# aq_mx_v1-4-0b.net
KiCad netlist of a schematic drawn in EAGLE
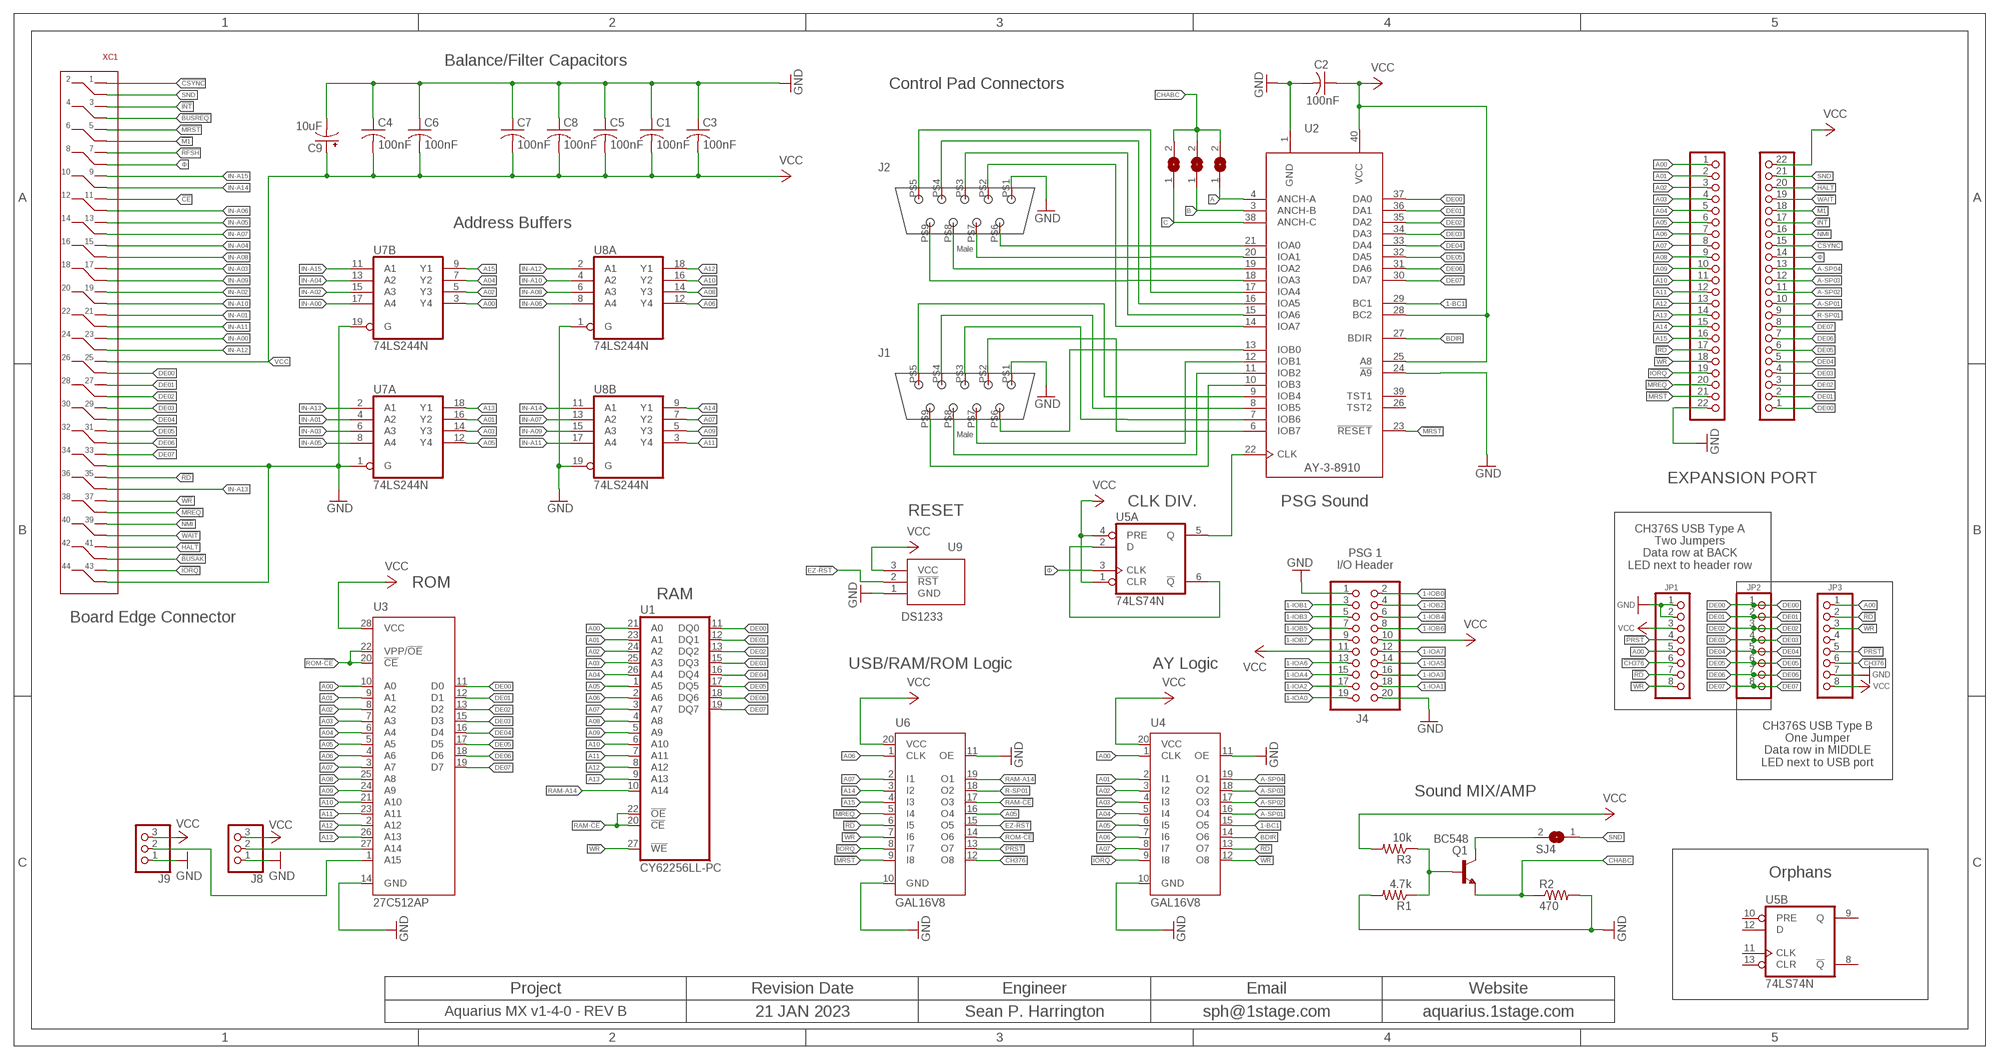
[diagram p0: schematic, sheet 1]

(export (version "E")
  (design (tool "Eeschema 10.0.6"))
  (components
    (comp (ref "C1")
      (value "100nF")
      (footprint "eagle-import:C050-025X075")
      (libsource (lib "eagle-import") (part "C-US050-025X075"))
    )
    (comp (ref "C2")
      (value "100nF")
      (footprint "eagle-import:C050-025X075")
      (libsource (lib "eagle-import") (part "C-US050-025X075"))
    )
    (comp (ref "C3")
      (value "100nF")
      (footprint "eagle-import:C050-025X075")
      (libsource (lib "eagle-import") (part "C-US050-025X075"))
    )
    (comp (ref "C4")
      (value "100nF")
      (footprint "eagle-import:C050-025X075")
      (libsource (lib "eagle-import") (part "C-US050-025X075"))
    )
    (comp (ref "C5")
      (value "100nF")
      (footprint "eagle-import:C050-025X075")
      (libsource (lib "eagle-import") (part "C-US050-025X075"))
    )
    (comp (ref "C6")
      (value "100nF")
      (footprint "eagle-import:C050-025X075")
      (libsource (lib "eagle-import") (part "C-US050-025X075"))
    )
    (comp (ref "C7")
      (value "100nF")
      (footprint "eagle-import:C050-025X075")
      (libsource (lib "eagle-import") (part "C-US050-025X075"))
    )
    (comp (ref "C8")
      (value "100nF")
      (footprint "eagle-import:C050-025X075")
      (libsource (lib "eagle-import") (part "C-US050-025X075"))
    )
    (comp (ref "C9")
      (value "10uF")
      (footprint "eagle-import:E22-6")
      (libsource (lib "eagle-import") (part "CPOL-USE22-6AXIAL"))
    )
    (comp (ref "J1")
      (value "DB9-MALE-RA")
      (footprint "eagle-import:DB9-MALE-RA")
      (libsource (lib "eagle-import") (part "DB9-MALE-RA"))
    )
    (comp (ref "J2")
      (value "DB9-MALE-RA")
      (footprint "eagle-import:DB9-MALE-RA")
      (libsource (lib "eagle-import") (part "DB9-MALE-RA"))
    )
    (comp (ref "J4")
      (value "PINHD-2X10")
      (footprint "eagle-import:2X10")
      (libsource (lib "eagle-import") (part "PINHD-2X10"))
    )
    (comp (ref "J6")
      (value "PINHD-1X22")
      (footprint "eagle-import:1X22")
      (libsource (lib "eagle-import") (part "PINHD-1X22"))
    )
    (comp (ref "J7")
      (value "PINHD-1X22")
      (footprint "eagle-import:1X22")
      (libsource (lib "eagle-import") (part "PINHD-1X22"))
    )
    (comp (ref "J8")
      (value "PINHD-1X3")
      (footprint "eagle-import:1X03")
      (libsource (lib "eagle-import") (part "PINHD-1X3"))
    )
    (comp (ref "J9")
      (value "PINHD-1X3")
      (footprint "eagle-import:1X03")
      (libsource (lib "eagle-import") (part "PINHD-1X3"))
    )
    (comp (ref "JP1")
      (value "PINHD-1X8")
      (footprint "eagle-import:1X08")
      (libsource (lib "eagle-import") (part "PINHD-1X8"))
    )
    (comp (ref "JP2")
      (value "PINHD-1X8")
      (footprint "eagle-import:1X08")
      (libsource (lib "eagle-import") (part "PINHD-1X8"))
    )
    (comp (ref "JP3")
      (value "PINHD-1X8")
      (footprint "eagle-import:1X08")
      (libsource (lib "eagle-import") (part "PINHD-1X8"))
    )
    (comp (ref "Q1")
      (value "BC548")
      (footprint "eagle-import:TO92-CBE")
      (libsource (lib "eagle-import") (part "-NPN-TO92-CBEBC548"))
    )
    (comp (ref "R1")
      (value "4.7k")
      (footprint "eagle-import:0204_7")
      (libsource (lib "eagle-import") (part "R-US_0204/7"))
    )
    (comp (ref "R2")
      (value "470")
      (footprint "eagle-import:0204_7")
      (libsource (lib "eagle-import") (part "R-US_0204/7"))
    )
    (comp (ref "R3")
      (value "10k")
      (footprint "eagle-import:0204_7")
      (libsource (lib "eagle-import") (part "R-US_0204/7"))
    )
    (comp (ref "SJ1") (value "SJ") (footprint "eagle-import:SJ") (libsource (lib "eagle-import") (part "SJ")))
    (comp (ref "SJ2") (value "SJ") (footprint "eagle-import:SJ") (libsource (lib "eagle-import") (part "SJ")))
    (comp (ref "SJ3") (value "SJ") (footprint "eagle-import:SJ") (libsource (lib "eagle-import") (part "SJ")))
    (comp (ref "SJ4") (value "SJ") (footprint "eagle-import:SJ") (libsource (lib "eagle-import") (part "SJ")))
    (comp (ref "U1")
      (value "CY62256LL-PC")
      (footprint "eagle-import:DIL28-6")
      (libsource (lib "eagle-import") (part "CY62256LL-?PC"))
    )
    (comp (ref "U2")
      (value "AY-3-8910")
      (footprint "eagle-import:RAD38910-DIL40-6")
      (libsource (lib "eagle-import") (part "RAD38910DIL40-6"))
    )
    (comp (ref "U3")
      (value "27C512AP")
      (footprint "eagle-import:DIL28-6")
      (fields (field (name "MPN") "M27C512-90B6"))
      (libsource (lib "eagle-import") (part "27512APC"))
    )
    (comp (ref "U4")
      (value "GAL16V8")
      (footprint "eagle-import:DIL20")
      (fields (field (name "MPN") "ATF16V8CZ-15PU"))
      (libsource (lib "eagle-import") (part "ATF16V8BP3"))
    )
    (comp (ref "U5")
      (value "74LS74N")
      (footprint "eagle-import:DIL14")
      (libsource (lib "eagle-import") (part "7474NLS"))
    )
    (comp (ref "U6")
      (value "GAL16V8")
      (footprint "eagle-import:DIL20")
      (fields (field (name "MPN") "ATF16V8CZ-15PU"))
      (libsource (lib "eagle-import") (part "ATF16V8BP3"))
    )
    (comp (ref "U7")
      (value "74LS244N")
      (footprint "eagle-import:DIL20")
      (libsource (lib "eagle-import") (part "74244NLS"))
    )
    (comp (ref "U8")
      (value "74LS244N")
      (footprint "eagle-import:DIL20")
      (libsource (lib "eagle-import") (part "74244NLS"))
    )
    (comp (ref "U9")
      (value "DS1233")
      (footprint "eagle-import:TO-92")
      (fields
        (field (name "ARROW_PART_NUMBER") "DS1233-10+")
        (field (name "MOUSER_PART_NUMBER") "700-DS1233-10")
      )
      (libsource (lib "eagle-import") (part "DS1233-10+"))
    )
    (comp (ref "XC1")
      (value "AQ-CART-EDGE")
      (footprint "eagle-import:AQ-CART-EDGE")
      (libsource (lib "eagle-import") (part "AQ-CART-EDGE"))
    )
  )
  (nets
    (net (code "1") (name "/EZ-~{RST}") (class "Default")
      (node (ref "U6") (pin "15") (pinfunction "O5_15") (pintype "output"))
      (node (ref "U9") (pin "2") (pinfunction "~{RST}_2") (pintype "input"))
    )
    (net (code "2") (name "/RAM-~{CE}") (class "Default")
      (node (ref "U1") (pin "20") (pinfunction "~{CE}_20") (pintype "input"))
      (node (ref "U1") (pin "22") (pinfunction "~{OE}_22") (pintype "input"))
      (node (ref "U6") (pin "17") (pinfunction "O3_17") (pintype "output"))
    )
    (net (code "3") (name "/ROM-~{CE}") (class "Default")
      (node (ref "U3") (pin "20") (pinfunction "~{CE}_20") (pintype "input"))
      (node (ref "U3") (pin "22") (pinfunction "VPP/~{OE}_22") (pintype "input"))
      (node (ref "U6") (pin "14") (pinfunction "O6_14") (pintype "output"))
    )
    (net (code "4") (name "/~{BUSAK}") (class "Default")
      (node (ref "XC1") (pin "P$42") (pinfunction "X42_P$42") (pintype "bidirectional"))
    )
    (net (code "5") (name "/~{BUSREQ}") (class "Default")
      (node (ref "XC1") (pin "P$4") (pinfunction "X4_P$4") (pintype "bidirectional"))
    )
    (net (code "6") (name "/~{CE}") (class "Default")
      (node (ref "XC1") (pin "P$11") (pinfunction "X11_P$11") (pintype "bidirectional"))
    )
    (net (code "7") (name "/~{CH376}") (class "Default")
      (node (ref "JP1") (pin "6") (pinfunction "6_6") (pintype "passive"))
      (node (ref "JP3") (pin "6") (pinfunction "6_6") (pintype "passive"))
      (node (ref "U6") (pin "12") (pinfunction "O8_12") (pintype "output"))
    )
    (net (code "8") (name "/~{CSYNC}") (class "Default")
      (node (ref "J6") (pin "15") (pinfunction "15_15") (pintype "passive"))
      (node (ref "XC1") (pin "P$1") (pinfunction "X1_P$1") (pintype "bidirectional"))
    )
    (net (code "9") (name "/~{HALT}") (class "Default")
      (node (ref "J6") (pin "20") (pinfunction "20_20") (pintype "passive"))
      (node (ref "XC1") (pin "P$41") (pinfunction "X41_P$41") (pintype "bidirectional"))
    )
    (net (code "10") (name "/~{INT}") (class "Default")
      (node (ref "J6") (pin "17") (pinfunction "17_17") (pintype "passive"))
      (node (ref "XC1") (pin "P$3") (pinfunction "X3_P$3") (pintype "bidirectional"))
    )
    (net (code "11") (name "/~{IORQ}") (class "Default")
      (node (ref "J7") (pin "19") (pinfunction "19_19") (pintype "passive"))
      (node (ref "U4") (pin "9") (pinfunction "I8_9") (pintype "input"))
      (node (ref "U6") (pin "8") (pinfunction "I7_8") (pintype "input"))
      (node (ref "XC1") (pin "P$43") (pinfunction "X43_P$43") (pintype "bidirectional"))
    )
    (net (code "12") (name "/~{M1}") (class "Default")
      (node (ref "J6") (pin "18") (pinfunction "18_18") (pintype "passive"))
      (node (ref "XC1") (pin "P$6") (pinfunction "X6_P$6") (pintype "bidirectional"))
    )
    (net (code "13") (name "/~{MREQ}") (class "Default")
      (node (ref "J7") (pin "20") (pinfunction "20_20") (pintype "passive"))
      (node (ref "U6") (pin "5") (pinfunction "I4_5") (pintype "input"))
      (node (ref "XC1") (pin "P$38") (pinfunction "X38_P$38") (pintype "bidirectional"))
    )
    (net (code "14") (name "/~{MRST}") (class "Default")
      (node (ref "J7") (pin "21") (pinfunction "21_21") (pintype "passive"))
      (node (ref "U2") (pin "23") (pinfunction "~{RESET}_23") (pintype "bidirectional"))
      (node (ref "U6") (pin "9") (pinfunction "I8_9") (pintype "input"))
      (node (ref "XC1") (pin "P$5") (pinfunction "X5_P$5") (pintype "bidirectional"))
    )
    (net (code "15") (name "/~{NMI}") (class "Default")
      (node (ref "J6") (pin "16") (pinfunction "16_16") (pintype "passive"))
      (node (ref "XC1") (pin "P$39") (pinfunction "X39_P$39") (pintype "bidirectional"))
    )
    (net (code "16") (name "/~{PRST}") (class "Default")
      (node (ref "JP1") (pin "4") (pinfunction "4_4") (pintype "passive"))
      (node (ref "JP3") (pin "5") (pinfunction "5_5") (pintype "passive"))
      (node (ref "U6") (pin "13") (pinfunction "O7_13") (pintype "output"))
    )
    (net (code "17") (name "/~{RD}") (class "Default")
      (node (ref "J7") (pin "17") (pinfunction "17_17") (pintype "passive"))
      (node (ref "JP1") (pin "7") (pinfunction "7_7") (pintype "passive"))
      (node (ref "JP3") (pin "2") (pinfunction "2_2") (pintype "passive"))
      (node (ref "U4") (pin "13") (pinfunction "O7_13") (pintype "output"))
      (node (ref "U6") (pin "6") (pinfunction "I5_6") (pintype "input"))
      (node (ref "XC1") (pin "P$35") (pinfunction "X35_P$35") (pintype "bidirectional"))
    )
    (net (code "18") (name "/~{RFSH}") (class "Default")
      (node (ref "XC1") (pin "P$7") (pinfunction "X7_P$7") (pintype "bidirectional"))
    )
    (net (code "19") (name "/~{WAIT}") (class "Default")
      (node (ref "J6") (pin "19") (pinfunction "19_19") (pintype "passive"))
      (node (ref "XC1") (pin "P$40") (pinfunction "X40_P$40") (pintype "bidirectional"))
    )
    (net (code "20") (name "/~{WR}") (class "Default")
      (node (ref "J7") (pin "18") (pinfunction "18_18") (pintype "passive"))
      (node (ref "JP1") (pin "8") (pinfunction "8_8") (pintype "passive"))
      (node (ref "JP3") (pin "3") (pinfunction "3_3") (pintype "passive"))
      (node (ref "U1") (pin "27") (pinfunction "~{WE}_27") (pintype "input"))
      (node (ref "U4") (pin "12") (pinfunction "O8_12") (pintype "output"))
      (node (ref "U6") (pin "7") (pinfunction "I6_7") (pintype "input"))
      (node (ref "XC1") (pin "P$37") (pinfunction "X37_P$37") (pintype "bidirectional"))
    )
    (net (code "21") (name "1-BC1") (class "Default")
      (node (ref "U2") (pin "29") (pinfunction "BC1_29") (pintype "bidirectional"))
      (node (ref "U4") (pin "15") (pinfunction "O5_15") (pintype "output"))
    )
    (net (code "22") (name "1-IOA0") (class "Default")
      (node (ref "J2") (pin "P$6") (pinfunction "P$6_P$6") (pintype "bidirectional"))
      (node (ref "J4") (pin "19") (pinfunction "19_19") (pintype "passive"))
      (node (ref "U2") (pin "21") (pinfunction "IOA0_21") (pintype "bidirectional"))
    )
    (net (code "23") (name "1-IOA1") (class "Default")
      (node (ref "J2") (pin "P$7") (pinfunction "P$7_P$7") (pintype "bidirectional"))
      (node (ref "J4") (pin "18") (pinfunction "18_18") (pintype "passive"))
      (node (ref "U2") (pin "20") (pinfunction "IOA1_20") (pintype "bidirectional"))
    )
    (net (code "24") (name "1-IOA2") (class "Default")
      (node (ref "J2") (pin "P$8") (pinfunction "P$8_P$8") (pintype "bidirectional"))
      (node (ref "J4") (pin "17") (pinfunction "17_17") (pintype "passive"))
      (node (ref "U2") (pin "19") (pinfunction "IOA2_19") (pintype "bidirectional"))
    )
    (net (code "25") (name "1-IOA3") (class "Default")
      (node (ref "J2") (pin "P$9") (pinfunction "P$9_P$9") (pintype "bidirectional"))
      (node (ref "J4") (pin "16") (pinfunction "16_16") (pintype "passive"))
      (node (ref "U2") (pin "18") (pinfunction "IOA3_18") (pintype "bidirectional"))
    )
    (net (code "26") (name "1-IOA4") (class "Default")
      (node (ref "J2") (pin "P$5") (pinfunction "P$5_P$5") (pintype "bidirectional"))
      (node (ref "J4") (pin "15") (pinfunction "15_15") (pintype "passive"))
      (node (ref "U2") (pin "17") (pinfunction "IOA4_17") (pintype "bidirectional"))
    )
    (net (code "27") (name "1-IOA5") (class "Default")
      (node (ref "J2") (pin "P$4") (pinfunction "P$4_P$4") (pintype "bidirectional"))
      (node (ref "J4") (pin "14") (pinfunction "14_14") (pintype "passive"))
      (node (ref "U2") (pin "16") (pinfunction "IOA5_16") (pintype "bidirectional"))
    )
    (net (code "28") (name "1-IOA6") (class "Default")
      (node (ref "J2") (pin "P$3") (pinfunction "P$3_P$3") (pintype "bidirectional"))
      (node (ref "J4") (pin "13") (pinfunction "13_13") (pintype "passive"))
      (node (ref "U2") (pin "15") (pinfunction "IOA6_15") (pintype "bidirectional"))
    )
    (net (code "29") (name "1-IOA7") (class "Default")
      (node (ref "J2") (pin "P$2") (pinfunction "P$2_P$2") (pintype "bidirectional"))
      (node (ref "J4") (pin "12") (pinfunction "12_12") (pintype "passive"))
      (node (ref "U2") (pin "14") (pinfunction "IOA7_14") (pintype "bidirectional"))
    )
    (net (code "30") (name "1-IOB0") (class "Default")
      (node (ref "J1") (pin "P$6") (pinfunction "P$6_P$6") (pintype "bidirectional"))
      (node (ref "J4") (pin "2") (pinfunction "2_2") (pintype "passive"))
      (node (ref "U2") (pin "13") (pinfunction "IOB0_13") (pintype "bidirectional"))
    )
    (net (code "31") (name "1-IOB1") (class "Default")
      (node (ref "J1") (pin "P$7") (pinfunction "P$7_P$7") (pintype "bidirectional"))
      (node (ref "J4") (pin "3") (pinfunction "3_3") (pintype "passive"))
      (node (ref "U2") (pin "12") (pinfunction "IOB1_12") (pintype "bidirectional"))
    )
    (net (code "32") (name "1-IOB2") (class "Default")
      (node (ref "J1") (pin "P$8") (pinfunction "P$8_P$8") (pintype "bidirectional"))
      (node (ref "J4") (pin "4") (pinfunction "4_4") (pintype "passive"))
      (node (ref "U2") (pin "11") (pinfunction "IOB2_11") (pintype "bidirectional"))
    )
    (net (code "33") (name "1-IOB3") (class "Default")
      (node (ref "J1") (pin "P$9") (pinfunction "P$9_P$9") (pintype "bidirectional"))
      (node (ref "J4") (pin "5") (pinfunction "5_5") (pintype "passive"))
      (node (ref "U2") (pin "10") (pinfunction "IOB3_10") (pintype "bidirectional"))
    )
    (net (code "34") (name "1-IOB4") (class "Default")
      (node (ref "J1") (pin "P$5") (pinfunction "P$5_P$5") (pintype "bidirectional"))
      (node (ref "J4") (pin "6") (pinfunction "6_6") (pintype "passive"))
      (node (ref "U2") (pin "9") (pinfunction "IOB4_9") (pintype "bidirectional"))
    )
    (net (code "35") (name "1-IOB5") (class "Default")
      (node (ref "J1") (pin "P$4") (pinfunction "P$4_P$4") (pintype "bidirectional"))
      (node (ref "J4") (pin "7") (pinfunction "7_7") (pintype "passive"))
      (node (ref "U2") (pin "8") (pinfunction "IOB5_8") (pintype "bidirectional"))
    )
    (net (code "36") (name "1-IOB6") (class "Default")
      (node (ref "J1") (pin "P$3") (pinfunction "P$3_P$3") (pintype "bidirectional"))
      (node (ref "J4") (pin "8") (pinfunction "8_8") (pintype "passive"))
      (node (ref "U2") (pin "7") (pinfunction "IOB6_7") (pintype "bidirectional"))
    )
    (net (code "37") (name "1-IOB7") (class "Default")
      (node (ref "J1") (pin "P$2") (pinfunction "P$2_P$2") (pintype "bidirectional"))
      (node (ref "J4") (pin "9") (pinfunction "9_9") (pintype "passive"))
      (node (ref "U2") (pin "6") (pinfunction "IOB7_6") (pintype "bidirectional"))
    )
    (net (code "38") (name "A") (class "Default")
      (node (ref "SJ1") (pin "1") (pinfunction "1_1") (pintype "passive"))
      (node (ref "U2") (pin "4") (pinfunction "ANCH-A_4") (pintype "bidirectional"))
    )
    (net (code "39") (name "A-SP01") (class "Default")
      (node (ref "J6") (pin "10") (pinfunction "10_10") (pintype "passive"))
      (node (ref "U4") (pin "16") (pinfunction "O4_16") (pintype "output"))
    )
    (net (code "40") (name "A-SP02") (class "Default")
      (node (ref "J6") (pin "11") (pinfunction "11_11") (pintype "passive"))
      (node (ref "U4") (pin "17") (pinfunction "O3_17") (pintype "output"))
    )
    (net (code "41") (name "A-SP03") (class "Default")
      (node (ref "J6") (pin "12") (pinfunction "12_12") (pintype "passive"))
      (node (ref "U4") (pin "18") (pinfunction "O2_18") (pintype "output"))
    )
    (net (code "42") (name "A-SP04") (class "Default")
      (node (ref "J6") (pin "13") (pinfunction "13_13") (pintype "passive"))
      (node (ref "U4") (pin "19") (pinfunction "O1_19") (pintype "output"))
    )
    (net (code "43") (name "A00") (class "Default")
      (node (ref "J7") (pin "1") (pinfunction "1_1") (pintype "passive"))
      (node (ref "JP1") (pin "5") (pinfunction "5_5") (pintype "passive"))
      (node (ref "JP3") (pin "1") (pinfunction "1_1") (pintype "passive"))
      (node (ref "U1") (pin "21") (pinfunction "A0_21") (pintype "input"))
      (node (ref "U3") (pin "10") (pinfunction "A0_10") (pintype "input"))
      (node (ref "U4") (pin "1") (pinfunction "CLK_1") (pintype "input"))
      (node (ref "U7") (pin "3") (pinfunction "Y4_3") (pintype "tri_state"))
    )
    (net (code "44") (name "A01") (class "Default")
      (node (ref "J7") (pin "2") (pinfunction "2_2") (pintype "passive"))
      (node (ref "U1") (pin "23") (pinfunction "A1_23") (pintype "input"))
      (node (ref "U3") (pin "9") (pinfunction "A1_9") (pintype "input"))
      (node (ref "U4") (pin "2") (pinfunction "I1_2") (pintype "input"))
      (node (ref "U7") (pin "16") (pinfunction "Y2_16") (pintype "tri_state"))
    )
    (net (code "45") (name "A02") (class "Default")
      (node (ref "J7") (pin "3") (pinfunction "3_3") (pintype "passive"))
      (node (ref "U1") (pin "24") (pinfunction "A2_24") (pintype "input"))
      (node (ref "U3") (pin "8") (pinfunction "A2_8") (pintype "input"))
      (node (ref "U4") (pin "3") (pinfunction "I2_3") (pintype "input"))
      (node (ref "U7") (pin "5") (pinfunction "Y3_5") (pintype "tri_state"))
    )
    (net (code "46") (name "A03") (class "Default")
      (node (ref "J7") (pin "4") (pinfunction "4_4") (pintype "passive"))
      (node (ref "U1") (pin "25") (pinfunction "A3_25") (pintype "input"))
      (node (ref "U3") (pin "7") (pinfunction "A3_7") (pintype "input"))
      (node (ref "U4") (pin "4") (pinfunction "I3_4") (pintype "input"))
      (node (ref "U7") (pin "14") (pinfunction "Y3_14") (pintype "tri_state"))
    )
    (net (code "47") (name "A04") (class "Default")
      (node (ref "J7") (pin "5") (pinfunction "5_5") (pintype "passive"))
      (node (ref "U1") (pin "26") (pinfunction "A4_26") (pintype "input"))
      (node (ref "U3") (pin "6") (pinfunction "A4_6") (pintype "input"))
      (node (ref "U4") (pin "5") (pinfunction "I4_5") (pintype "input"))
      (node (ref "U7") (pin "7") (pinfunction "Y2_7") (pintype "tri_state"))
    )
    (net (code "48") (name "A05") (class "Default")
      (node (ref "J7") (pin "6") (pinfunction "6_6") (pintype "passive"))
      (node (ref "U1") (pin "1") (pinfunction "A5_1") (pintype "input"))
      (node (ref "U3") (pin "5") (pinfunction "A5_5") (pintype "input"))
      (node (ref "U4") (pin "6") (pinfunction "I5_6") (pintype "input"))
      (node (ref "U6") (pin "16") (pinfunction "O4_16") (pintype "output"))
      (node (ref "U7") (pin "12") (pinfunction "Y4_12") (pintype "tri_state"))
    )
    (net (code "49") (name "A06") (class "Default")
      (node (ref "J7") (pin "7") (pinfunction "7_7") (pintype "passive"))
      (node (ref "U1") (pin "2") (pinfunction "A6_2") (pintype "input"))
      (node (ref "U3") (pin "4") (pinfunction "A6_4") (pintype "input"))
      (node (ref "U4") (pin "7") (pinfunction "I6_7") (pintype "input"))
      (node (ref "U6") (pin "1") (pinfunction "CLK_1") (pintype "input"))
      (node (ref "U8") (pin "12") (pinfunction "Y4_12") (pintype "tri_state"))
    )
    (net (code "50") (name "A07") (class "Default")
      (node (ref "J7") (pin "8") (pinfunction "8_8") (pintype "passive"))
      (node (ref "U1") (pin "3") (pinfunction "A7_3") (pintype "input"))
      (node (ref "U3") (pin "3") (pinfunction "A7_3") (pintype "input"))
      (node (ref "U4") (pin "8") (pinfunction "I7_8") (pintype "input"))
      (node (ref "U6") (pin "2") (pinfunction "I1_2") (pintype "input"))
      (node (ref "U8") (pin "7") (pinfunction "Y2_7") (pintype "tri_state"))
    )
    (net (code "51") (name "A08") (class "Default")
      (node (ref "J7") (pin "9") (pinfunction "9_9") (pintype "passive"))
      (node (ref "U1") (pin "4") (pinfunction "A8_4") (pintype "input"))
      (node (ref "U3") (pin "25") (pinfunction "A8_25") (pintype "input"))
      (node (ref "U8") (pin "14") (pinfunction "Y3_14") (pintype "tri_state"))
    )
    (net (code "52") (name "A09") (class "Default")
      (node (ref "J7") (pin "10") (pinfunction "10_10") (pintype "passive"))
      (node (ref "U1") (pin "5") (pinfunction "A9_5") (pintype "input"))
      (node (ref "U3") (pin "24") (pinfunction "A9_24") (pintype "input"))
      (node (ref "U8") (pin "5") (pinfunction "Y3_5") (pintype "tri_state"))
    )
    (net (code "53") (name "A10") (class "Default")
      (node (ref "J7") (pin "11") (pinfunction "11_11") (pintype "passive"))
      (node (ref "U1") (pin "6") (pinfunction "A10_6") (pintype "input"))
      (node (ref "U3") (pin "21") (pinfunction "A10_21") (pintype "input"))
      (node (ref "U8") (pin "16") (pinfunction "Y2_16") (pintype "tri_state"))
    )
    (net (code "54") (name "A11") (class "Default")
      (node (ref "J7") (pin "12") (pinfunction "12_12") (pintype "passive"))
      (node (ref "U1") (pin "7") (pinfunction "A11_7") (pintype "input"))
      (node (ref "U3") (pin "23") (pinfunction "A11_23") (pintype "input"))
      (node (ref "U8") (pin "3") (pinfunction "Y4_3") (pintype "tri_state"))
    )
    (net (code "55") (name "A12") (class "Default")
      (node (ref "J7") (pin "13") (pinfunction "13_13") (pintype "passive"))
      (node (ref "U1") (pin "8") (pinfunction "A12_8") (pintype "input"))
      (node (ref "U3") (pin "2") (pinfunction "A12_2") (pintype "input"))
      (node (ref "U8") (pin "18") (pinfunction "Y1_18") (pintype "tri_state"))
    )
    (net (code "56") (name "A13") (class "Default")
      (node (ref "J7") (pin "14") (pinfunction "14_14") (pintype "passive"))
      (node (ref "U1") (pin "9") (pinfunction "A13_9") (pintype "input"))
      (node (ref "U3") (pin "26") (pinfunction "A13_26") (pintype "input"))
      (node (ref "U7") (pin "18") (pinfunction "Y1_18") (pintype "tri_state"))
    )
    (net (code "57") (name "A14") (class "Default")
      (node (ref "J7") (pin "15") (pinfunction "15_15") (pintype "passive"))
      (node (ref "U6") (pin "3") (pinfunction "I2_3") (pintype "input"))
      (node (ref "U8") (pin "9") (pinfunction "Y1_9") (pintype "tri_state"))
    )
    (net (code "58") (name "A15") (class "Default")
      (node (ref "J7") (pin "16") (pinfunction "16_16") (pintype "passive"))
      (node (ref "U6") (pin "4") (pinfunction "I3_4") (pintype "input"))
      (node (ref "U7") (pin "9") (pinfunction "Y1_9") (pintype "tri_state"))
    )
    (net (code "59") (name "B") (class "Default")
      (node (ref "SJ2") (pin "1") (pinfunction "1_1") (pintype "passive"))
      (node (ref "U2") (pin "3") (pinfunction "ANCH-B_3") (pintype "bidirectional"))
    )
    (net (code "60") (name "BDIR") (class "Default")
      (node (ref "U2") (pin "27") (pinfunction "BDIR_27") (pintype "bidirectional"))
      (node (ref "U4") (pin "14") (pinfunction "O6_14") (pintype "output"))
    )
    (net (code "61") (name "C") (class "Default")
      (node (ref "SJ3") (pin "1") (pinfunction "1_1") (pintype "passive"))
      (node (ref "U2") (pin "38") (pinfunction "ANCH-C_38") (pintype "bidirectional"))
    )
    (net (code "62") (name "CHABC") (class "Default")
      (node (ref "Q1") (pin "E") (pinfunction "E_E") (pintype "passive"))
      (node (ref "R2") (pin "1") (pinfunction "1_1") (pintype "passive"))
      (node (ref "SJ1") (pin "2") (pinfunction "2_2") (pintype "passive"))
      (node (ref "SJ2") (pin "2") (pinfunction "2_2") (pintype "passive"))
      (node (ref "SJ3") (pin "2") (pinfunction "2_2") (pintype "passive"))
    )
    (net (code "63") (name "DE00") (class "Default")
      (node (ref "J6") (pin "1") (pinfunction "1_1") (pintype "passive"))
      (node (ref "JP2") (pin "1") (pinfunction "1_1") (pintype "passive"))
      (node (ref "U1") (pin "11") (pinfunction "DQ0_11") (pintype "bidirectional"))
      (node (ref "U2") (pin "37") (pinfunction "DA0_37") (pintype "bidirectional"))
      (node (ref "U3") (pin "11") (pinfunction "D0_11") (pintype "tri_state"))
      (node (ref "XC1") (pin "P$26") (pinfunction "X26_P$26") (pintype "bidirectional"))
    )
    (net (code "64") (name "DE01") (class "Default")
      (node (ref "J6") (pin "2") (pinfunction "2_2") (pintype "passive"))
      (node (ref "JP2") (pin "2") (pinfunction "2_2") (pintype "passive"))
      (node (ref "U1") (pin "12") (pinfunction "DQ1_12") (pintype "bidirectional"))
      (node (ref "U2") (pin "36") (pinfunction "DA1_36") (pintype "bidirectional"))
      (node (ref "U3") (pin "12") (pinfunction "D1_12") (pintype "tri_state"))
      (node (ref "XC1") (pin "P$27") (pinfunction "X27_P$27") (pintype "bidirectional"))
    )
    (net (code "65") (name "DE02") (class "Default")
      (node (ref "J6") (pin "3") (pinfunction "3_3") (pintype "passive"))
      (node (ref "JP2") (pin "3") (pinfunction "3_3") (pintype "passive"))
      (node (ref "U1") (pin "13") (pinfunction "DQ2_13") (pintype "bidirectional"))
      (node (ref "U2") (pin "35") (pinfunction "DA2_35") (pintype "bidirectional"))
      (node (ref "U3") (pin "13") (pinfunction "D2_13") (pintype "tri_state"))
      (node (ref "XC1") (pin "P$28") (pinfunction "X28_P$28") (pintype "bidirectional"))
    )
    (net (code "66") (name "DE03") (class "Default")
      (node (ref "J6") (pin "4") (pinfunction "4_4") (pintype "passive"))
      (node (ref "JP2") (pin "4") (pinfunction "4_4") (pintype "passive"))
      (node (ref "U1") (pin "15") (pinfunction "DQ3_15") (pintype "bidirectional"))
      (node (ref "U2") (pin "34") (pinfunction "DA3_34") (pintype "bidirectional"))
      (node (ref "U3") (pin "15") (pinfunction "D3_15") (pintype "tri_state"))
      (node (ref "XC1") (pin "P$29") (pinfunction "X29_P$29") (pintype "bidirectional"))
    )
    (net (code "67") (name "DE04") (class "Default")
      (node (ref "J6") (pin "5") (pinfunction "5_5") (pintype "passive"))
      (node (ref "JP2") (pin "5") (pinfunction "5_5") (pintype "passive"))
      (node (ref "U1") (pin "16") (pinfunction "DQ4_16") (pintype "bidirectional"))
      (node (ref "U2") (pin "33") (pinfunction "DA4_33") (pintype "bidirectional"))
      (node (ref "U3") (pin "16") (pinfunction "D4_16") (pintype "tri_state"))
      (node (ref "XC1") (pin "P$30") (pinfunction "X30_P$30") (pintype "bidirectional"))
    )
    (net (code "68") (name "DE05") (class "Default")
      (node (ref "J6") (pin "6") (pinfunction "6_6") (pintype "passive"))
      (node (ref "JP2") (pin "6") (pinfunction "6_6") (pintype "passive"))
      (node (ref "U1") (pin "17") (pinfunction "DQ5_17") (pintype "bidirectional"))
      (node (ref "U2") (pin "32") (pinfunction "DA5_32") (pintype "bidirectional"))
      (node (ref "U3") (pin "17") (pinfunction "D5_17") (pintype "tri_state"))
      (node (ref "XC1") (pin "P$31") (pinfunction "X31_P$31") (pintype "bidirectional"))
    )
    (net (code "69") (name "DE06") (class "Default")
      (node (ref "J6") (pin "7") (pinfunction "7_7") (pintype "passive"))
      (node (ref "JP2") (pin "7") (pinfunction "7_7") (pintype "passive"))
      (node (ref "U1") (pin "18") (pinfunction "DQ6_18") (pintype "bidirectional"))
      (node (ref "U2") (pin "31") (pinfunction "DA6_31") (pintype "bidirectional"))
      (node (ref "U3") (pin "18") (pinfunction "D6_18") (pintype "tri_state"))
      (node (ref "XC1") (pin "P$32") (pinfunction "X32_P$32") (pintype "bidirectional"))
    )
    (net (code "70") (name "DE07") (class "Default")
      (node (ref "J6") (pin "8") (pinfunction "8_8") (pintype "passive"))
      (node (ref "JP2") (pin "8") (pinfunction "8_8") (pintype "passive"))
      (node (ref "U1") (pin "19") (pinfunction "DQ7_19") (pintype "bidirectional"))
      (node (ref "U2") (pin "30") (pinfunction "DA7_30") (pintype "bidirectional"))
      (node (ref "U3") (pin "19") (pinfunction "D7_19") (pintype "tri_state"))
      (node (ref "XC1") (pin "P$33") (pinfunction "X33_P$33") (pintype "bidirectional"))
    )
    (net (code "71") (name "GND") (class "Default")
      (node (ref "C1") (pin "1") (pinfunction "1_1") (pintype "passive"))
      (node (ref "C2") (pin "2") (pinfunction "2_2") (pintype "passive"))
      (node (ref "C3") (pin "1") (pinfunction "1_1") (pintype "passive"))
      (node (ref "C4") (pin "1") (pinfunction "1_1") (pintype "passive"))
      (node (ref "C5") (pin "1") (pinfunction "1_1") (pintype "passive"))
      (node (ref "C6") (pin "1") (pinfunction "1_1") (pintype "passive"))
      (node (ref "C7") (pin "1") (pinfunction "1_1") (pintype "passive"))
      (node (ref "C8") (pin "1") (pinfunction "1_1") (pintype "passive"))
      (node (ref "C9") (pin "-") (pinfunction "-_-") (pintype "passive"))
      (node (ref "J1") (pin "P$1") (pinfunction "P$1_P$1") (pintype "bidirectional"))
      (node (ref "J2") (pin "P$1") (pinfunction "P$1_P$1") (pintype "bidirectional"))
      (node (ref "J4") (pin "1") (pinfunction "1_1") (pintype "passive"))
      (node (ref "J4") (pin "20") (pinfunction "20_20") (pintype "passive"))
      (node (ref "J7") (pin "22") (pinfunction "22_22") (pintype "passive"))
      (node (ref "J8") (pin "1") (pinfunction "1_1") (pintype "passive"))
      (node (ref "J9") (pin "1") (pinfunction "1_1") (pintype "passive"))
      (node (ref "JP1") (pin "1") (pinfunction "1_1") (pintype "passive"))
      (node (ref "JP1") (pin "2") (pinfunction "2_2") (pintype "passive"))
      (node (ref "JP3") (pin "7") (pinfunction "7_7") (pintype "passive"))
      (node (ref "R1") (pin "2") (pinfunction "2_2") (pintype "passive"))
      (node (ref "R2") (pin "2") (pinfunction "2_2") (pintype "passive"))
      (node (ref "U2") (pin "1") (pinfunction "GND_1") (pintype "power_in"))
      (node (ref "U2") (pin "24") (pinfunction "~{A9}_24") (pintype "bidirectional"))
      (node (ref "U3") (pin "14") (pinfunction "GND_14") (pintype "power_in"))
      (node (ref "U4") (pin "10") (pinfunction "GND_10") (pintype "power_in"))
      (node (ref "U4") (pin "11") (pinfunction "OE_11") (pintype "input"))
      (node (ref "U6") (pin "10") (pinfunction "GND_10") (pintype "power_in"))
      (node (ref "U6") (pin "11") (pinfunction "OE_11") (pintype "input"))
      (node (ref "U7") (pin "1") (pinfunction "G_1") (pintype "input"))
      (node (ref "U7") (pin "19") (pinfunction "G_19") (pintype "input"))
      (node (ref "U8") (pin "1") (pinfunction "G_1") (pintype "input"))
      (node (ref "U8") (pin "19") (pinfunction "G_19") (pintype "input"))
      (node (ref "U9") (pin "1") (pinfunction "GND_1") (pintype "power_in"))
      (node (ref "XC1") (pin "P$34") (pinfunction "X34_P$34") (pintype "bidirectional"))
      (node (ref "XC1") (pin "P$44") (pinfunction "X44_P$44") (pintype "bidirectional"))
    )
    (net (code "72") (name "IN-A00") (class "Default")
      (node (ref "U7") (pin "17") (pinfunction "A4_17") (pintype "input"))
      (node (ref "XC1") (pin "P$23") (pinfunction "X23_P$23") (pintype "bidirectional"))
    )
    (net (code "73") (name "IN-A01") (class "Default")
      (node (ref "U7") (pin "4") (pinfunction "A2_4") (pintype "input"))
      (node (ref "XC1") (pin "P$21") (pinfunction "X21_P$21") (pintype "bidirectional"))
    )
    (net (code "74") (name "IN-A02") (class "Default")
      (node (ref "U7") (pin "15") (pinfunction "A3_15") (pintype "input"))
      (node (ref "XC1") (pin "P$19") (pinfunction "X19_P$19") (pintype "bidirectional"))
    )
    (net (code "75") (name "IN-A03") (class "Default")
      (node (ref "U7") (pin "6") (pinfunction "A3_6") (pintype "input"))
      (node (ref "XC1") (pin "P$17") (pinfunction "X17_P$17") (pintype "bidirectional"))
    )
    (net (code "76") (name "IN-A04") (class "Default")
      (node (ref "U7") (pin "13") (pinfunction "A2_13") (pintype "input"))
      (node (ref "XC1") (pin "P$15") (pinfunction "X15_P$15") (pintype "bidirectional"))
    )
    (net (code "77") (name "IN-A05") (class "Default")
      (node (ref "U7") (pin "8") (pinfunction "A4_8") (pintype "input"))
      (node (ref "XC1") (pin "P$13") (pinfunction "X13_P$13") (pintype "bidirectional"))
    )
    (net (code "78") (name "IN-A06") (class "Default")
      (node (ref "U8") (pin "8") (pinfunction "A4_8") (pintype "input"))
      (node (ref "XC1") (pin "P$12") (pinfunction "X12_P$12") (pintype "bidirectional"))
    )
    (net (code "79") (name "IN-A07") (class "Default")
      (node (ref "U8") (pin "13") (pinfunction "A2_13") (pintype "input"))
      (node (ref "XC1") (pin "P$14") (pinfunction "X14_P$14") (pintype "bidirectional"))
    )
    (net (code "80") (name "IN-A08") (class "Default")
      (node (ref "U8") (pin "6") (pinfunction "A3_6") (pintype "input"))
      (node (ref "XC1") (pin "P$16") (pinfunction "X16_P$16") (pintype "bidirectional"))
    )
    (net (code "81") (name "IN-A09") (class "Default")
      (node (ref "U8") (pin "15") (pinfunction "A3_15") (pintype "input"))
      (node (ref "XC1") (pin "P$18") (pinfunction "X18_P$18") (pintype "bidirectional"))
    )
    (net (code "82") (name "IN-A10") (class "Default")
      (node (ref "U8") (pin "4") (pinfunction "A2_4") (pintype "input"))
      (node (ref "XC1") (pin "P$20") (pinfunction "X20_P$20") (pintype "bidirectional"))
    )
    (net (code "83") (name "IN-A11") (class "Default")
      (node (ref "U8") (pin "17") (pinfunction "A4_17") (pintype "input"))
      (node (ref "XC1") (pin "P$22") (pinfunction "X22_P$22") (pintype "bidirectional"))
    )
    (net (code "84") (name "IN-A12") (class "Default")
      (node (ref "U8") (pin "2") (pinfunction "A1_2") (pintype "input"))
      (node (ref "XC1") (pin "P$24") (pinfunction "X24_P$24") (pintype "bidirectional"))
    )
    (net (code "85") (name "IN-A13") (class "Default")
      (node (ref "U7") (pin "2") (pinfunction "A1_2") (pintype "input"))
      (node (ref "XC1") (pin "P$36") (pinfunction "X36_P$36") (pintype "bidirectional"))
    )
    (net (code "86") (name "IN-A14") (class "Default")
      (node (ref "U8") (pin "11") (pinfunction "A1_11") (pintype "input"))
      (node (ref "XC1") (pin "P$10") (pinfunction "X10_P$10") (pintype "bidirectional"))
    )
    (net (code "87") (name "IN-A15") (class "Default")
      (node (ref "U7") (pin "11") (pinfunction "A1_11") (pintype "input"))
      (node (ref "XC1") (pin "P$9") (pinfunction "X9_P$9") (pintype "bidirectional"))
    )
    (net (code "88") (name "Net-(Q1-PadB)") (class "Default")
      (node (ref "Q1") (pin "B") (pinfunction "B_B") (pintype "passive"))
      (node (ref "R1") (pin "1") (pinfunction "1_1") (pintype "passive"))
      (node (ref "R3") (pin "1") (pinfunction "1_1") (pintype "passive"))
    )
    (net (code "89") (name "Net-(Q1-PadC)") (class "Default")
      (node (ref "Q1") (pin "C") (pinfunction "C_C") (pintype "passive"))
      (node (ref "SJ4") (pin "2") (pinfunction "2_2") (pintype "passive"))
    )
    (net (code "90") (name "Net-(U2-CLK)") (class "Default")
      (node (ref "U2") (pin "22") (pinfunction "CLK_22") (pintype "input"))
      (node (ref "U5") (pin "5") (pinfunction "Q_5") (pintype "output"))
    )
    (net (code "91") (name "Net-(U3-A14)") (class "Default")
      (node (ref "J8") (pin "2") (pinfunction "2_2") (pintype "passive"))
      (node (ref "U3") (pin "27") (pinfunction "A14_27") (pintype "input"))
    )
    (net (code "92") (name "Net-(U3-A15)") (class "Default")
      (node (ref "J9") (pin "2") (pinfunction "2_2") (pintype "passive"))
      (node (ref "U3") (pin "1") (pinfunction "A15_1") (pintype "input"))
    )
    (net (code "93") (name "Net-(U5A-D)") (class "Default")
      (node (ref "U5") (pin "2") (pinfunction "D_2") (pintype "input"))
      (node (ref "U5") (pin "6") (pinfunction "~{Q}_6") (pintype "output"))
    )
    (net (code "94") (name "R-SP01") (class "Default")
      (node (ref "J6") (pin "9") (pinfunction "9_9") (pintype "passive"))
      (node (ref "U6") (pin "18") (pinfunction "O2_18") (pintype "output"))
    )
    (net (code "95") (name "RAM-A14") (class "Default")
      (node (ref "U1") (pin "10") (pinfunction "A14_10") (pintype "input"))
      (node (ref "U6") (pin "19") (pinfunction "O1_19") (pintype "output"))
    )
    (net (code "96") (name "SND") (class "Default")
      (node (ref "J6") (pin "21") (pinfunction "21_21") (pintype "passive"))
      (node (ref "SJ4") (pin "1") (pinfunction "1_1") (pintype "passive"))
      (node (ref "XC1") (pin "P$2") (pinfunction "X2_P$2") (pintype "bidirectional"))
    )
    (net (code "97") (name "VCC") (class "Default")
      (node (ref "C1") (pin "2") (pinfunction "2_2") (pintype "passive"))
      (node (ref "C2") (pin "1") (pinfunction "1_1") (pintype "passive"))
      (node (ref "C3") (pin "2") (pinfunction "2_2") (pintype "passive"))
      (node (ref "C4") (pin "2") (pinfunction "2_2") (pintype "passive"))
      (node (ref "C5") (pin "2") (pinfunction "2_2") (pintype "passive"))
      (node (ref "C6") (pin "2") (pinfunction "2_2") (pintype "passive"))
      (node (ref "C7") (pin "2") (pinfunction "2_2") (pintype "passive"))
      (node (ref "C8") (pin "2") (pinfunction "2_2") (pintype "passive"))
      (node (ref "C9") (pin "+") (pinfunction "+_+") (pintype "passive"))
      (node (ref "J4") (pin "10") (pinfunction "10_10") (pintype "passive"))
      (node (ref "J4") (pin "11") (pinfunction "11_11") (pintype "passive"))
      (node (ref "J6") (pin "22") (pinfunction "22_22") (pintype "passive"))
      (node (ref "J8") (pin "3") (pinfunction "3_3") (pintype "passive"))
      (node (ref "J9") (pin "3") (pinfunction "3_3") (pintype "passive"))
      (node (ref "JP1") (pin "3") (pinfunction "3_3") (pintype "passive"))
      (node (ref "JP3") (pin "8") (pinfunction "8_8") (pintype "passive"))
      (node (ref "R3") (pin "2") (pinfunction "2_2") (pintype "passive"))
      (node (ref "U2") (pin "25") (pinfunction "A8_25") (pintype "bidirectional"))
      (node (ref "U2") (pin "28") (pinfunction "BC2_28") (pintype "bidirectional"))
      (node (ref "U2") (pin "40") (pinfunction "VCC_40") (pintype "power_in"))
      (node (ref "U3") (pin "28") (pinfunction "VCC_28") (pintype "power_in"))
      (node (ref "U4") (pin "20") (pinfunction "VCC_20") (pintype "power_in"))
      (node (ref "U5") (pin "1") (pinfunction "CLR_1") (pintype "input"))
      (node (ref "U5") (pin "4") (pinfunction "PRE_4") (pintype "input"))
      (node (ref "U6") (pin "20") (pinfunction "VCC_20") (pintype "power_in"))
      (node (ref "U9") (pin "3") (pinfunction "VCC_3") (pintype "power_in"))
      (node (ref "XC1") (pin "P$25") (pinfunction "X25_P$25") (pintype "bidirectional"))
    )
    (net (code "98") (name "unconnected-(JP3-Pad4)") (class "Default")
      (node (ref "JP3") (pin "4") (pinfunction "4_4") (pintype "passive"))
    )
    (net (code "99") (name "unconnected-(U2-TST1-Pad39)") (class "Default")
      (node (ref "U2") (pin "39") (pinfunction "TST1_39") (pintype "bidirectional"))
    )
    (net (code "100") (name "unconnected-(U2-TST2-Pad26)") (class "Default")
      (node (ref "U2") (pin "26") (pinfunction "TST2_26") (pintype "bidirectional"))
    )
    (net (code "101") (name "unconnected-(U5B-CLK-Pad11)") (class "Default")
      (node (ref "U5") (pin "11") (pinfunction "CLK_11") (pintype "input"))
    )
    (net (code "102") (name "unconnected-(U5B-CLR-Pad13)") (class "Default")
      (node (ref "U5") (pin "13") (pinfunction "CLR_13") (pintype "input"))
    )
    (net (code "103") (name "unconnected-(U5B-D-Pad12)") (class "Default")
      (node (ref "U5") (pin "12") (pinfunction "D_12") (pintype "input"))
    )
    (net (code "104") (name "unconnected-(U5B-PRE-Pad10)") (class "Default")
      (node (ref "U5") (pin "10") (pinfunction "PRE_10") (pintype "input"))
    )
    (net (code "105") (name "unconnected-(U5B-Q-Pad9)") (class "Default")
      (node (ref "U5") (pin "9") (pinfunction "Q_9") (pintype "output"))
    )
    (net (code "106") (name "unconnected-(U5B-~{Q}-Pad8)") (class "Default")
      (node (ref "U5") (pin "8") (pinfunction "~{Q}_8") (pintype "output"))
    )
    (net (code "107") (name "Φ") (class "Default")
      (node (ref "J6") (pin "14") (pinfunction "14_14") (pintype "passive"))
      (node (ref "U5") (pin "3") (pinfunction "CLK_3") (pintype "input"))
      (node (ref "XC1") (pin "P$8") (pinfunction "X8_P$8") (pintype "bidirectional"))
    )
  )
)
